# MSV-front.net
KiCad netlist of a schematic drawn in EAGLE
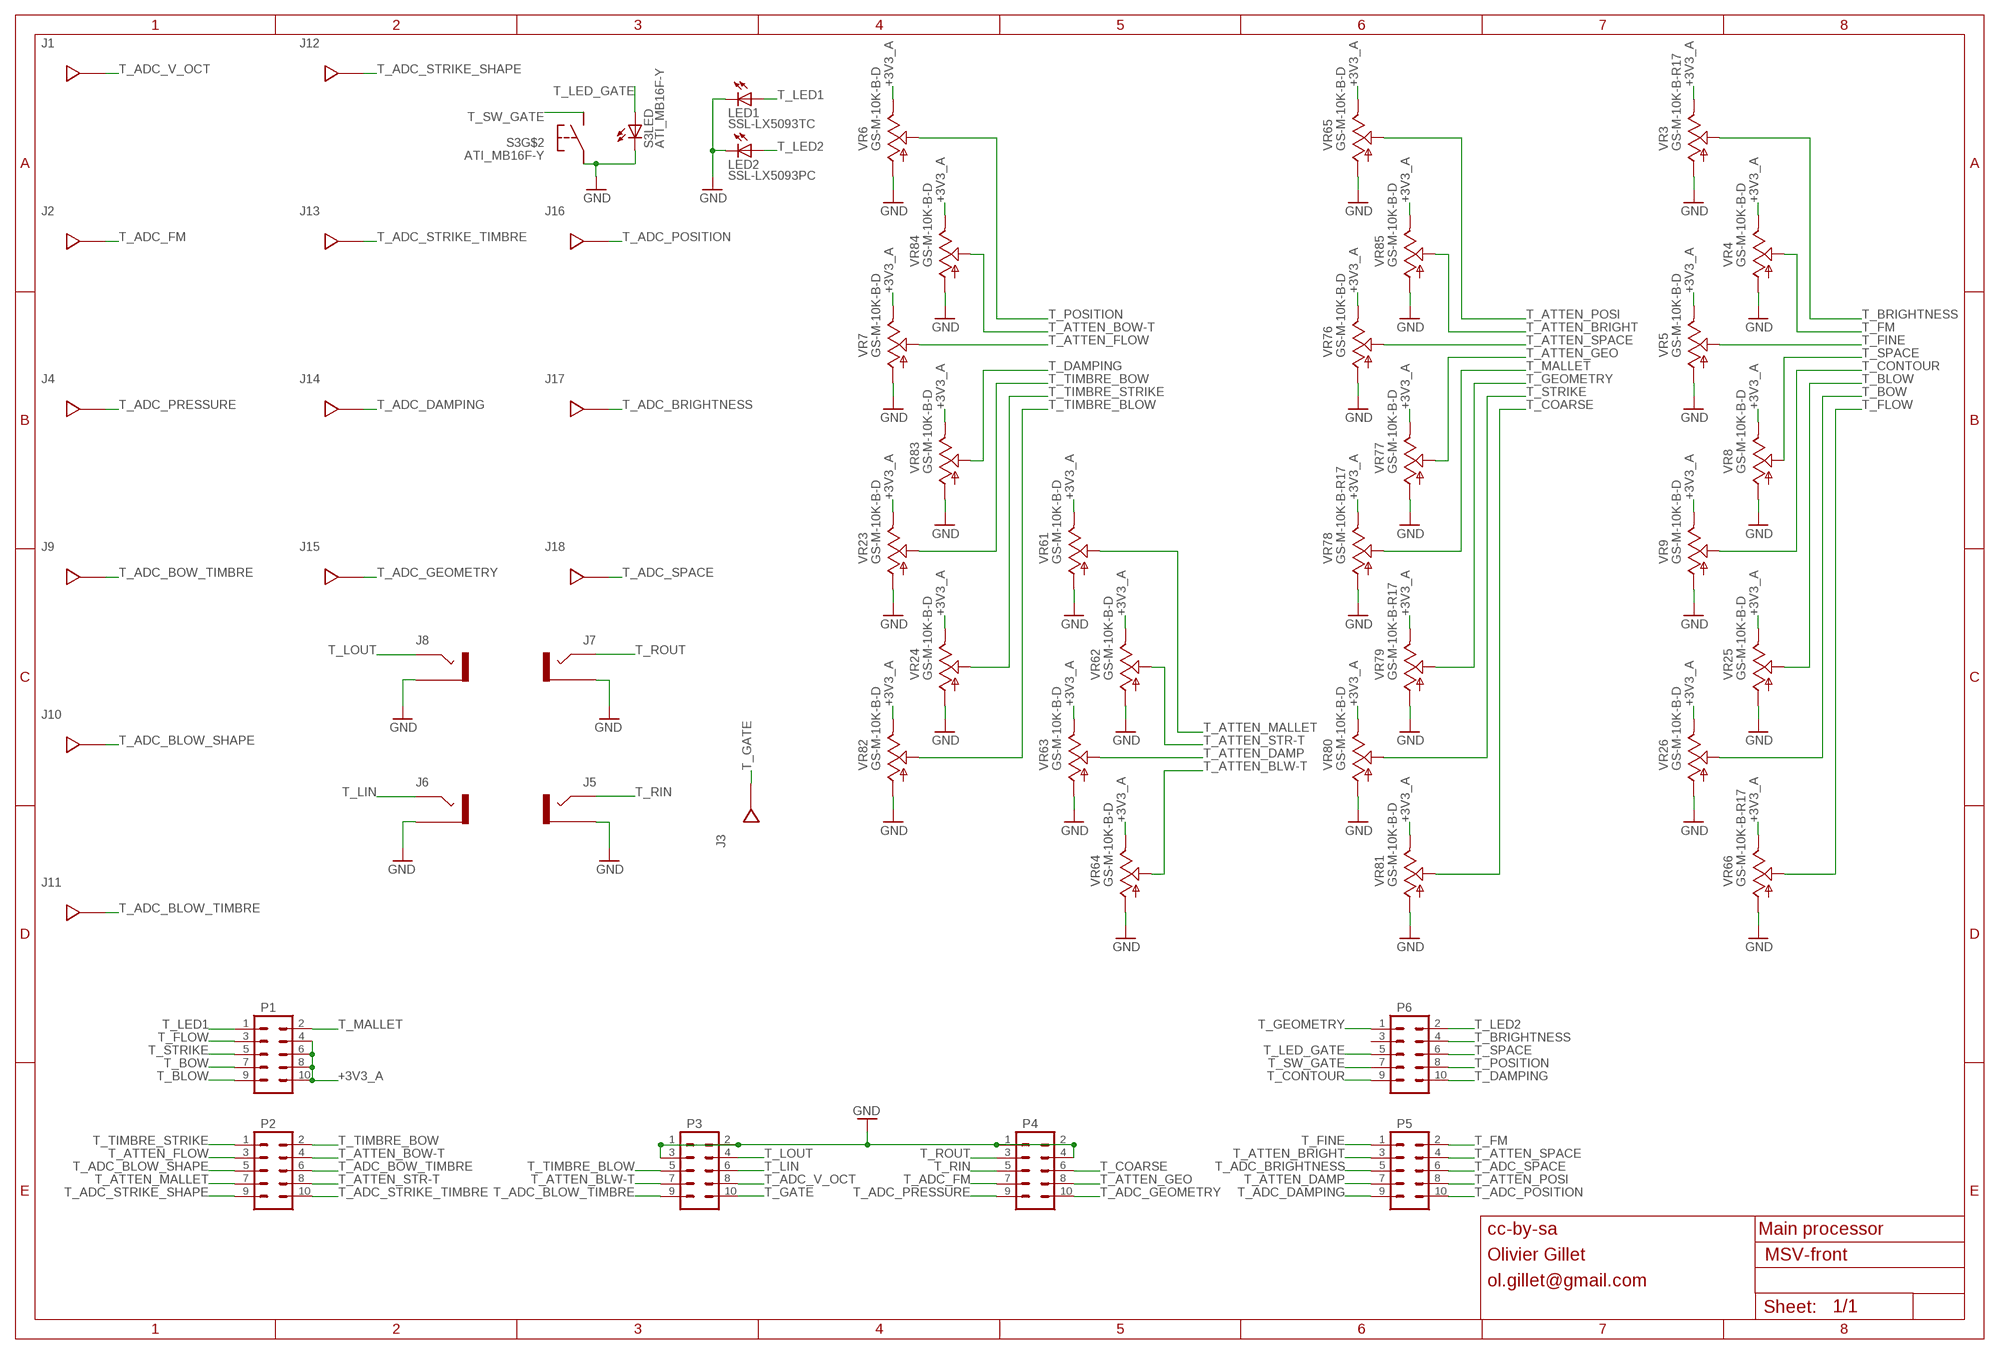
[diagram p0: schematic, sheet 1]

(export (version "E")
  (design (tool "Eeschema 10.0.6"))
  (components
    (comp (ref "J1")
      (value "BANANA_JACK_GRAY")
      (footprint "eagle-import:JOHNSON_SILK")
      (libsource (lib "eagle-import") (part "BANANA_JACK_GRAY"))
    )
    (comp (ref "J2")
      (value "BANANA_JACK_BLACK")
      (footprint "eagle-import:JOHNSON_SILK")
      (libsource (lib "eagle-import") (part "BANANA_JACK_BLACK"))
    )
    (comp (ref "J3")
      (value "BANANA_JACK_ORANGE")
      (footprint "eagle-import:JOHNSON_SILK")
      (libsource (lib "eagle-import") (part "BANANA_JACK_ORANGE"))
    )
    (comp (ref "J4")
      (value "BANANA_JACK_BLACK")
      (footprint "eagle-import:JOHNSON_SILK")
      (libsource (lib "eagle-import") (part "BANANA_JACK_BLACK"))
    )
    (comp (ref "J5")
      (value "BUCHLA_AUDIO_JACK_ALT")
      (footprint "eagle-import:AUDIO_ALT")
      (fields (field (name "LABEL") "RES"))
      (libsource (lib "eagle-import") (part "BUCHLA_AUDIO_JACK_ALT"))
    )
    (comp (ref "J6")
      (value "BUCHLA_AUDIO_JACK_ALT")
      (footprint "eagle-import:AUDIO_ALT")
      (fields (field (name "LABEL") "EXC"))
      (libsource (lib "eagle-import") (part "BUCHLA_AUDIO_JACK_ALT"))
    )
    (comp (ref "J7")
      (value "BUCHLA_AUDIO_JACK_ALT")
      (footprint "eagle-import:AUDIO_ALT")
      (fields (field (name "LABEL") "OUT2"))
      (libsource (lib "eagle-import") (part "BUCHLA_AUDIO_JACK_ALT"))
    )
    (comp (ref "J8")
      (value "BUCHLA_AUDIO_JACK_ALT")
      (footprint "eagle-import:AUDIO_ALT")
      (fields (field (name "LABEL") "OUT1"))
      (libsource (lib "eagle-import") (part "BUCHLA_AUDIO_JACK_ALT"))
    )
    (comp (ref "J9")
      (value "BANANA_JACK_BLACK")
      (footprint "eagle-import:JOHNSON_SILK")
      (libsource (lib "eagle-import") (part "BANANA_JACK_BLACK"))
    )
    (comp (ref "J10")
      (value "BANANA_JACK_BLACK")
      (footprint "eagle-import:JOHNSON_SILK")
      (libsource (lib "eagle-import") (part "BANANA_JACK_BLACK"))
    )
    (comp (ref "J11")
      (value "BANANA_JACK_BLACK")
      (footprint "eagle-import:JOHNSON_SILK")
      (libsource (lib "eagle-import") (part "BANANA_JACK_BLACK"))
    )
    (comp (ref "J12")
      (value "BANANA_JACK_BLACK")
      (footprint "eagle-import:JOHNSON_SILK")
      (libsource (lib "eagle-import") (part "BANANA_JACK_BLACK"))
    )
    (comp (ref "J13")
      (value "BANANA_JACK_BLACK")
      (footprint "eagle-import:JOHNSON_SILK")
      (libsource (lib "eagle-import") (part "BANANA_JACK_BLACK"))
    )
    (comp (ref "J14")
      (value "BANANA_JACK_BLACK")
      (footprint "eagle-import:JOHNSON_SILK")
      (libsource (lib "eagle-import") (part "BANANA_JACK_BLACK"))
    )
    (comp (ref "J15")
      (value "BANANA_JACK_BLACK")
      (footprint "eagle-import:JOHNSON_SILK")
      (libsource (lib "eagle-import") (part "BANANA_JACK_BLACK"))
    )
    (comp (ref "J16")
      (value "BANANA_JACK_BLACK")
      (footprint "eagle-import:JOHNSON_SILK")
      (libsource (lib "eagle-import") (part "BANANA_JACK_BLACK"))
    )
    (comp (ref "J17")
      (value "BANANA_JACK_BLACK")
      (footprint "eagle-import:JOHNSON_SILK")
      (libsource (lib "eagle-import") (part "BANANA_JACK_BLACK"))
    )
    (comp (ref "J18")
      (value "BANANA_JACK_BLACK")
      (footprint "eagle-import:JOHNSON_SILK")
      (libsource (lib "eagle-import") (part "BANANA_JACK_BLACK"))
    )
    (comp (ref "LED1")
      (value "SSL-LX5093TC")
      (footprint "eagle-import:LED_SILK")
      (libsource (lib "eagle-import") (part "LED_SILK"))
    )
    (comp (ref "LED2")
      (value "SSL-LX5093PC")
      (footprint "eagle-import:LED_SILK")
      (libsource (lib "eagle-import") (part "LED_SILK"))
    )
    (comp (ref "P1")
      (value "M05X2_LOCK_FEMALE")
      (footprint "eagle-import:2X5_LOCK_FEMALE")
      (libsource (lib "eagle-import") (part "M05X2_LOCK_FEMALE"))
    )
    (comp (ref "P2")
      (value "M05X2_LOCK_FEMALE")
      (footprint "eagle-import:2X5_LOCK_FEMALE")
      (libsource (lib "eagle-import") (part "M05X2_LOCK_FEMALE"))
    )
    (comp (ref "P3")
      (value "M05X2_LOCK_FEMALE")
      (footprint "eagle-import:2X5_LOCK_FEMALE")
      (libsource (lib "eagle-import") (part "M05X2_LOCK_FEMALE"))
    )
    (comp (ref "P4")
      (value "M05X2_LOCK_FEMALE")
      (footprint "eagle-import:2X5_LOCK_FEMALE")
      (libsource (lib "eagle-import") (part "M05X2_LOCK_FEMALE"))
    )
    (comp (ref "P5")
      (value "M05X2_LOCK_FEMALE")
      (footprint "eagle-import:2X5_LOCK_FEMALE")
      (libsource (lib "eagle-import") (part "M05X2_LOCK_FEMALE"))
    )
    (comp (ref "P6")
      (value "M05X2_LOCK_FEMALE")
      (footprint "eagle-import:2X5_LOCK_FEMALE")
      (libsource (lib "eagle-import") (part "M05X2_LOCK_FEMALE"))
    )
    (comp (ref "S3")
      (value "ATI_MB16F-Y")
      (footprint "eagle-import:MB16F_SILK")
      (libsource (lib "eagle-import") (part "ATI_MB16F-Y"))
    )
    (comp (ref "VR3")
      (value "GS-M-10K-B-R17")
      (footprint "eagle-import:9MM_SNAP-IN_POT_SILK")
      (libsource (lib "eagle-import") (part "POT_9MM_SNAP-IN__"))
    )
    (comp (ref "VR4")
      (value "GS-M-10K-B-D")
      (footprint "eagle-import:9MM_SNAP-IN_POT_SILK")
      (libsource (lib "eagle-import") (part "POT_9MM_SNAP-IN__"))
    )
    (comp (ref "VR5")
      (value "GS-M-10K-B-D")
      (footprint "eagle-import:9MM_SNAP-IN_POT_SILK")
      (libsource (lib "eagle-import") (part "POT_9MM_SNAP-IN__"))
    )
    (comp (ref "VR6")
      (value "GS-M-10K-B-D")
      (footprint "eagle-import:9MM_SNAP-IN_POT_SILK")
      (libsource (lib "eagle-import") (part "POT_9MM_SNAP-IN__"))
    )
    (comp (ref "VR7")
      (value "GS-M-10K-B-D")
      (footprint "eagle-import:9MM_SNAP-IN_POT_SILK")
      (libsource (lib "eagle-import") (part "POT_9MM_SNAP-IN__"))
    )
    (comp (ref "VR8")
      (value "GS-M-10K-B-D")
      (footprint "eagle-import:9MM_SNAP-IN_POT_SILK")
      (libsource (lib "eagle-import") (part "POT_9MM_SNAP-IN__"))
    )
    (comp (ref "VR9")
      (value "GS-M-10K-B-D")
      (footprint "eagle-import:9MM_SNAP-IN_POT_SILK")
      (libsource (lib "eagle-import") (part "POT_9MM_SNAP-IN__"))
    )
    (comp (ref "VR23")
      (value "GS-M-10K-B-D")
      (footprint "eagle-import:9MM_SNAP-IN_POT_SILK")
      (libsource (lib "eagle-import") (part "POT_9MM_SNAP-IN__"))
    )
    (comp (ref "VR24")
      (value "GS-M-10K-B-D")
      (footprint "eagle-import:9MM_SNAP-IN_POT_SILK")
      (libsource (lib "eagle-import") (part "POT_9MM_SNAP-IN__"))
    )
    (comp (ref "VR25")
      (value "GS-M-10K-B-D")
      (footprint "eagle-import:9MM_SNAP-IN_POT_SILK")
      (libsource (lib "eagle-import") (part "POT_9MM_SNAP-IN__"))
    )
    (comp (ref "VR26")
      (value "GS-M-10K-B-D")
      (footprint "eagle-import:9MM_SNAP-IN_POT_SILK")
      (libsource (lib "eagle-import") (part "POT_9MM_SNAP-IN__"))
    )
    (comp (ref "VR61")
      (value "GS-M-10K-B-D")
      (footprint "eagle-import:9MM_SNAP-IN_POT_SILK")
      (libsource (lib "eagle-import") (part "POT_9MM_SNAP-IN__"))
    )
    (comp (ref "VR62")
      (value "GS-M-10K-B-D")
      (footprint "eagle-import:9MM_SNAP-IN_POT_SILK")
      (libsource (lib "eagle-import") (part "POT_9MM_SNAP-IN__"))
    )
    (comp (ref "VR63")
      (value "GS-M-10K-B-D")
      (footprint "eagle-import:9MM_SNAP-IN_POT_SILK")
      (libsource (lib "eagle-import") (part "POT_9MM_SNAP-IN__"))
    )
    (comp (ref "VR64")
      (value "GS-M-10K-B-D")
      (footprint "eagle-import:9MM_SNAP-IN_POT_SILK")
      (libsource (lib "eagle-import") (part "POT_9MM_SNAP-IN__"))
    )
    (comp (ref "VR65")
      (value "GS-M-10K-B-D")
      (footprint "eagle-import:9MM_SNAP-IN_POT_SILK")
      (libsource (lib "eagle-import") (part "POT_9MM_SNAP-IN__"))
    )
    (comp (ref "VR66")
      (value "GS-M-10K-B-R17")
      (footprint "eagle-import:9MM_SNAP-IN_POT_SILK")
      (libsource (lib "eagle-import") (part "POT_9MM_SNAP-IN__"))
    )
    (comp (ref "VR76")
      (value "GS-M-10K-B-D")
      (footprint "eagle-import:9MM_SNAP-IN_POT_SILK")
      (libsource (lib "eagle-import") (part "POT_9MM_SNAP-IN__"))
    )
    (comp (ref "VR77")
      (value "GS-M-10K-B-D")
      (footprint "eagle-import:9MM_SNAP-IN_POT_SILK")
      (libsource (lib "eagle-import") (part "POT_9MM_SNAP-IN__"))
    )
    (comp (ref "VR78")
      (value "GS-M-10K-B-R17")
      (footprint "eagle-import:9MM_SNAP-IN_POT_SILK")
      (libsource (lib "eagle-import") (part "POT_9MM_SNAP-IN__"))
    )
    (comp (ref "VR79")
      (value "GS-M-10K-B-R17")
      (footprint "eagle-import:9MM_SNAP-IN_POT_SILK")
      (libsource (lib "eagle-import") (part "POT_9MM_SNAP-IN__"))
    )
    (comp (ref "VR80")
      (value "GS-M-10K-B-D")
      (footprint "eagle-import:9MM_SNAP-IN_POT_SILK")
      (libsource (lib "eagle-import") (part "POT_9MM_SNAP-IN__"))
    )
    (comp (ref "VR81")
      (value "GS-M-10K-B-D")
      (footprint "eagle-import:9MM_SNAP-IN_POT_SILK")
      (libsource (lib "eagle-import") (part "POT_9MM_SNAP-IN__"))
    )
    (comp (ref "VR82")
      (value "GS-M-10K-B-D")
      (footprint "eagle-import:9MM_SNAP-IN_POT_SILK")
      (libsource (lib "eagle-import") (part "POT_9MM_SNAP-IN__"))
    )
    (comp (ref "VR83")
      (value "GS-M-10K-B-D")
      (footprint "eagle-import:9MM_SNAP-IN_POT_SILK")
      (libsource (lib "eagle-import") (part "POT_9MM_SNAP-IN__"))
    )
    (comp (ref "VR84")
      (value "GS-M-10K-B-D")
      (footprint "eagle-import:9MM_SNAP-IN_POT_SILK")
      (libsource (lib "eagle-import") (part "POT_9MM_SNAP-IN__"))
    )
    (comp (ref "VR85")
      (value "GS-M-10K-B-D")
      (footprint "eagle-import:9MM_SNAP-IN_POT_SILK")
      (libsource (lib "eagle-import") (part "POT_9MM_SNAP-IN__"))
    )
  )
  (nets
    (net (code "1") (name "/+3V3_A") (class "Default")
      (node (ref "P1") (pin "10") (pinfunction "10_10") (pintype "passive"))
      (node (ref "P1") (pin "4") (pinfunction "4_4") (pintype "passive"))
      (node (ref "P1") (pin "6") (pinfunction "6_6") (pintype "passive"))
      (node (ref "P1") (pin "8") (pinfunction "8_8") (pintype "passive"))
      (node (ref "VR23") (pin "3") (pinfunction "3_3") (pintype "passive"))
      (node (ref "VR24") (pin "3") (pinfunction "3_3") (pintype "passive"))
      (node (ref "VR25") (pin "3") (pinfunction "3_3") (pintype "passive"))
      (node (ref "VR26") (pin "3") (pinfunction "3_3") (pintype "passive"))
      (node (ref "VR3") (pin "3") (pinfunction "3_3") (pintype "passive"))
      (node (ref "VR4") (pin "3") (pinfunction "3_3") (pintype "passive"))
      (node (ref "VR5") (pin "3") (pinfunction "3_3") (pintype "passive"))
      (node (ref "VR6") (pin "3") (pinfunction "3_3") (pintype "passive"))
      (node (ref "VR61") (pin "3") (pinfunction "3_3") (pintype "passive"))
      (node (ref "VR62") (pin "3") (pinfunction "3_3") (pintype "passive"))
      (node (ref "VR63") (pin "3") (pinfunction "3_3") (pintype "passive"))
      (node (ref "VR64") (pin "3") (pinfunction "3_3") (pintype "passive"))
      (node (ref "VR65") (pin "3") (pinfunction "3_3") (pintype "passive"))
      (node (ref "VR66") (pin "3") (pinfunction "3_3") (pintype "passive"))
      (node (ref "VR7") (pin "3") (pinfunction "3_3") (pintype "passive"))
      (node (ref "VR76") (pin "3") (pinfunction "3_3") (pintype "passive"))
      (node (ref "VR77") (pin "3") (pinfunction "3_3") (pintype "passive"))
      (node (ref "VR78") (pin "3") (pinfunction "3_3") (pintype "passive"))
      (node (ref "VR79") (pin "3") (pinfunction "3_3") (pintype "passive"))
      (node (ref "VR8") (pin "3") (pinfunction "3_3") (pintype "passive"))
      (node (ref "VR80") (pin "3") (pinfunction "3_3") (pintype "passive"))
      (node (ref "VR81") (pin "3") (pinfunction "3_3") (pintype "passive"))
      (node (ref "VR82") (pin "3") (pinfunction "3_3") (pintype "passive"))
      (node (ref "VR83") (pin "3") (pinfunction "3_3") (pintype "passive"))
      (node (ref "VR84") (pin "3") (pinfunction "3_3") (pintype "passive"))
      (node (ref "VR85") (pin "3") (pinfunction "3_3") (pintype "passive"))
      (node (ref "VR9") (pin "3") (pinfunction "3_3") (pintype "passive"))
    )
    (net (code "2") (name "/T_ADC_BLOW_SHAPE") (class "Default")
      (node (ref "J10") (pin "1") (pinfunction "1_1") (pintype "output"))
      (node (ref "P2") (pin "5") (pinfunction "5_5") (pintype "passive"))
    )
    (net (code "3") (name "/T_ADC_BLOW_TIMBRE") (class "Default")
      (node (ref "J11") (pin "1") (pinfunction "1_1") (pintype "output"))
      (node (ref "P3") (pin "9") (pinfunction "9_9") (pintype "passive"))
    )
    (net (code "4") (name "/T_ADC_BOW_TIMBRE") (class "Default")
      (node (ref "J9") (pin "1") (pinfunction "1_1") (pintype "output"))
      (node (ref "P2") (pin "6") (pinfunction "6_6") (pintype "passive"))
    )
    (net (code "5") (name "/T_ADC_BRIGHTNESS") (class "Default")
      (node (ref "J17") (pin "1") (pinfunction "1_1") (pintype "output"))
      (node (ref "P5") (pin "5") (pinfunction "5_5") (pintype "passive"))
    )
    (net (code "6") (name "/T_ADC_DAMPING") (class "Default")
      (node (ref "J14") (pin "1") (pinfunction "1_1") (pintype "output"))
      (node (ref "P5") (pin "9") (pinfunction "9_9") (pintype "passive"))
    )
    (net (code "7") (name "/T_ADC_FM") (class "Default")
      (node (ref "J2") (pin "1") (pinfunction "1_1") (pintype "output"))
      (node (ref "P4") (pin "7") (pinfunction "7_7") (pintype "passive"))
    )
    (net (code "8") (name "/T_ADC_GEOMETRY") (class "Default")
      (node (ref "J15") (pin "1") (pinfunction "1_1") (pintype "output"))
      (node (ref "P4") (pin "10") (pinfunction "10_10") (pintype "passive"))
    )
    (net (code "9") (name "/T_ADC_POSITION") (class "Default")
      (node (ref "J16") (pin "1") (pinfunction "1_1") (pintype "output"))
      (node (ref "P5") (pin "10") (pinfunction "10_10") (pintype "passive"))
    )
    (net (code "10") (name "/T_ADC_PRESSURE") (class "Default")
      (node (ref "J4") (pin "1") (pinfunction "1_1") (pintype "output"))
      (node (ref "P4") (pin "9") (pinfunction "9_9") (pintype "passive"))
    )
    (net (code "11") (name "/T_ADC_SPACE") (class "Default")
      (node (ref "J18") (pin "1") (pinfunction "1_1") (pintype "output"))
      (node (ref "P5") (pin "6") (pinfunction "6_6") (pintype "passive"))
    )
    (net (code "12") (name "/T_ADC_STRIKE_SHAPE") (class "Default")
      (node (ref "J12") (pin "1") (pinfunction "1_1") (pintype "output"))
      (node (ref "P2") (pin "9") (pinfunction "9_9") (pintype "passive"))
    )
    (net (code "13") (name "/T_ADC_STRIKE_TIMBRE") (class "Default")
      (node (ref "J13") (pin "1") (pinfunction "1_1") (pintype "output"))
      (node (ref "P2") (pin "10") (pinfunction "10_10") (pintype "passive"))
    )
    (net (code "14") (name "/T_ADC_V_OCT") (class "Default")
      (node (ref "J1") (pin "1") (pinfunction "1_1") (pintype "output"))
      (node (ref "P3") (pin "8") (pinfunction "8_8") (pintype "passive"))
    )
    (net (code "15") (name "/T_ATTEN_BLW-T") (class "Default")
      (node (ref "P3") (pin "7") (pinfunction "7_7") (pintype "passive"))
      (node (ref "VR64") (pin "2") (pinfunction "2_2") (pintype "passive"))
    )
    (net (code "16") (name "/T_ATTEN_BOW-T") (class "Default")
      (node (ref "P2") (pin "4") (pinfunction "4_4") (pintype "passive"))
      (node (ref "VR84") (pin "2") (pinfunction "2_2") (pintype "passive"))
    )
    (net (code "17") (name "/T_ATTEN_BRIGHT") (class "Default")
      (node (ref "P5") (pin "3") (pinfunction "3_3") (pintype "passive"))
      (node (ref "VR85") (pin "2") (pinfunction "2_2") (pintype "passive"))
    )
    (net (code "18") (name "/T_ATTEN_DAMP") (class "Default")
      (node (ref "P5") (pin "7") (pinfunction "7_7") (pintype "passive"))
      (node (ref "VR63") (pin "2") (pinfunction "2_2") (pintype "passive"))
    )
    (net (code "19") (name "/T_ATTEN_FLOW") (class "Default")
      (node (ref "P2") (pin "3") (pinfunction "3_3") (pintype "passive"))
      (node (ref "VR7") (pin "2") (pinfunction "2_2") (pintype "passive"))
    )
    (net (code "20") (name "/T_ATTEN_GEO") (class "Default")
      (node (ref "P4") (pin "8") (pinfunction "8_8") (pintype "passive"))
      (node (ref "VR77") (pin "2") (pinfunction "2_2") (pintype "passive"))
    )
    (net (code "21") (name "/T_ATTEN_MALLET") (class "Default")
      (node (ref "P2") (pin "7") (pinfunction "7_7") (pintype "passive"))
      (node (ref "VR61") (pin "2") (pinfunction "2_2") (pintype "passive"))
    )
    (net (code "22") (name "/T_ATTEN_POSI") (class "Default")
      (node (ref "P5") (pin "8") (pinfunction "8_8") (pintype "passive"))
      (node (ref "VR65") (pin "2") (pinfunction "2_2") (pintype "passive"))
    )
    (net (code "23") (name "/T_ATTEN_SPACE") (class "Default")
      (node (ref "P5") (pin "4") (pinfunction "4_4") (pintype "passive"))
      (node (ref "VR76") (pin "2") (pinfunction "2_2") (pintype "passive"))
    )
    (net (code "24") (name "/T_ATTEN_STR-T") (class "Default")
      (node (ref "P2") (pin "8") (pinfunction "8_8") (pintype "passive"))
      (node (ref "VR62") (pin "2") (pinfunction "2_2") (pintype "passive"))
    )
    (net (code "25") (name "/T_BLOW") (class "Default")
      (node (ref "P1") (pin "9") (pinfunction "9_9") (pintype "passive"))
      (node (ref "VR25") (pin "2") (pinfunction "2_2") (pintype "passive"))
    )
    (net (code "26") (name "/T_BOW") (class "Default")
      (node (ref "P1") (pin "7") (pinfunction "7_7") (pintype "passive"))
      (node (ref "VR26") (pin "2") (pinfunction "2_2") (pintype "passive"))
    )
    (net (code "27") (name "/T_BRIGHTNESS") (class "Default")
      (node (ref "P6") (pin "4") (pinfunction "4_4") (pintype "passive"))
      (node (ref "VR3") (pin "2") (pinfunction "2_2") (pintype "passive"))
    )
    (net (code "28") (name "/T_COARSE") (class "Default")
      (node (ref "P4") (pin "6") (pinfunction "6_6") (pintype "passive"))
      (node (ref "VR81") (pin "2") (pinfunction "2_2") (pintype "passive"))
    )
    (net (code "29") (name "/T_CONTOUR") (class "Default")
      (node (ref "P6") (pin "9") (pinfunction "9_9") (pintype "passive"))
      (node (ref "VR9") (pin "2") (pinfunction "2_2") (pintype "passive"))
    )
    (net (code "30") (name "/T_DAMPING") (class "Default")
      (node (ref "P6") (pin "10") (pinfunction "10_10") (pintype "passive"))
      (node (ref "VR83") (pin "2") (pinfunction "2_2") (pintype "passive"))
    )
    (net (code "31") (name "/T_FINE") (class "Default")
      (node (ref "P5") (pin "1") (pinfunction "1_1") (pintype "passive"))
      (node (ref "VR5") (pin "2") (pinfunction "2_2") (pintype "passive"))
    )
    (net (code "32") (name "/T_FLOW") (class "Default")
      (node (ref "P1") (pin "3") (pinfunction "3_3") (pintype "passive"))
      (node (ref "VR66") (pin "2") (pinfunction "2_2") (pintype "passive"))
    )
    (net (code "33") (name "/T_FM") (class "Default")
      (node (ref "P5") (pin "2") (pinfunction "2_2") (pintype "passive"))
      (node (ref "VR4") (pin "2") (pinfunction "2_2") (pintype "passive"))
    )
    (net (code "34") (name "/T_GATE") (class "Default")
      (node (ref "J3") (pin "1") (pinfunction "1_1") (pintype "output"))
      (node (ref "P3") (pin "10") (pinfunction "10_10") (pintype "passive"))
    )
    (net (code "35") (name "/T_GEOMETRY") (class "Default")
      (node (ref "P6") (pin "1") (pinfunction "1_1") (pintype "passive"))
      (node (ref "VR79") (pin "2") (pinfunction "2_2") (pintype "passive"))
    )
    (net (code "36") (name "/T_LED1") (class "Default")
      (node (ref "LED1") (pin "A") (pinfunction "A_A") (pintype "passive"))
      (node (ref "P1") (pin "1") (pinfunction "1_1") (pintype "passive"))
    )
    (net (code "37") (name "/T_LED2") (class "Default")
      (node (ref "LED2") (pin "A") (pinfunction "A_A") (pintype "passive"))
      (node (ref "P6") (pin "2") (pinfunction "2_2") (pintype "passive"))
    )
    (net (code "38") (name "/T_LED_GATE") (class "Default")
      (node (ref "P6") (pin "5") (pinfunction "5_5") (pintype "passive"))
      (node (ref "S3") (pin "3") (pinfunction "L1_3") (pintype "passive"))
    )
    (net (code "39") (name "/T_LIN") (class "Default")
      (node (ref "J6") (pin "S") (pinfunction "1_S") (pintype "bidirectional"))
      (node (ref "P3") (pin "6") (pinfunction "6_6") (pintype "passive"))
    )
    (net (code "40") (name "/T_LOUT") (class "Default")
      (node (ref "J8") (pin "S") (pinfunction "1_S") (pintype "bidirectional"))
      (node (ref "P3") (pin "4") (pinfunction "4_4") (pintype "passive"))
    )
    (net (code "41") (name "/T_MALLET") (class "Default")
      (node (ref "P1") (pin "2") (pinfunction "2_2") (pintype "passive"))
      (node (ref "VR78") (pin "2") (pinfunction "2_2") (pintype "passive"))
    )
    (net (code "42") (name "/T_POSITION") (class "Default")
      (node (ref "P6") (pin "8") (pinfunction "8_8") (pintype "passive"))
      (node (ref "VR6") (pin "2") (pinfunction "2_2") (pintype "passive"))
    )
    (net (code "43") (name "/T_RIN") (class "Default")
      (node (ref "J5") (pin "S") (pinfunction "1_S") (pintype "bidirectional"))
      (node (ref "P4") (pin "5") (pinfunction "5_5") (pintype "passive"))
    )
    (net (code "44") (name "/T_ROUT") (class "Default")
      (node (ref "J7") (pin "S") (pinfunction "1_S") (pintype "bidirectional"))
      (node (ref "P4") (pin "3") (pinfunction "3_3") (pintype "passive"))
    )
    (net (code "45") (name "/T_SPACE") (class "Default")
      (node (ref "P6") (pin "6") (pinfunction "6_6") (pintype "passive"))
      (node (ref "VR8") (pin "2") (pinfunction "2_2") (pintype "passive"))
    )
    (net (code "46") (name "/T_STRIKE") (class "Default")
      (node (ref "P1") (pin "5") (pinfunction "5_5") (pintype "passive"))
      (node (ref "VR80") (pin "2") (pinfunction "2_2") (pintype "passive"))
    )
    (net (code "47") (name "/T_SW_GATE") (class "Default")
      (node (ref "P6") (pin "7") (pinfunction "7_7") (pintype "passive"))
      (node (ref "S3") (pin "1") (pinfunction "2_1") (pintype "passive"))
    )
    (net (code "48") (name "/T_TIMBRE_BLOW") (class "Default")
      (node (ref "P3") (pin "5") (pinfunction "5_5") (pintype "passive"))
      (node (ref "VR82") (pin "2") (pinfunction "2_2") (pintype "passive"))
    )
    (net (code "49") (name "/T_TIMBRE_BOW") (class "Default")
      (node (ref "P2") (pin "2") (pinfunction "2_2") (pintype "passive"))
      (node (ref "VR23") (pin "2") (pinfunction "2_2") (pintype "passive"))
    )
    (net (code "50") (name "/T_TIMBRE_STRIKE") (class "Default")
      (node (ref "P2") (pin "1") (pinfunction "1_1") (pintype "passive"))
      (node (ref "VR24") (pin "2") (pinfunction "2_2") (pintype "passive"))
    )
    (net (code "51") (name "GND") (class "Default")
      (node (ref "J5") (pin "G") (pinfunction "2_G") (pintype "bidirectional"))
      (node (ref "J6") (pin "G") (pinfunction "2_G") (pintype "bidirectional"))
      (node (ref "J7") (pin "G") (pinfunction "2_G") (pintype "bidirectional"))
      (node (ref "J8") (pin "G") (pinfunction "2_G") (pintype "bidirectional"))
      (node (ref "LED1") (pin "K") (pinfunction "C_K") (pintype "passive"))
      (node (ref "LED2") (pin "K") (pinfunction "C_K") (pintype "passive"))
      (node (ref "P3") (pin "1") (pinfunction "1_1") (pintype "passive"))
      (node (ref "P3") (pin "2") (pinfunction "2_2") (pintype "passive"))
      (node (ref "P3") (pin "3") (pinfunction "3_3") (pintype "passive"))
      (node (ref "P4") (pin "1") (pinfunction "1_1") (pintype "passive"))
      (node (ref "P4") (pin "2") (pinfunction "2_2") (pintype "passive"))
      (node (ref "P4") (pin "4") (pinfunction "4_4") (pintype "passive"))
      (node (ref "S3") (pin "2") (pinfunction "1_2") (pintype "passive"))
      (node (ref "S3") (pin "4") (pinfunction "L2_4") (pintype "passive"))
      (node (ref "VR23") (pin "1") (pinfunction "1_1") (pintype "passive"))
      (node (ref "VR24") (pin "1") (pinfunction "1_1") (pintype "passive"))
      (node (ref "VR25") (pin "1") (pinfunction "1_1") (pintype "passive"))
      (node (ref "VR26") (pin "1") (pinfunction "1_1") (pintype "passive"))
      (node (ref "VR3") (pin "1") (pinfunction "1_1") (pintype "passive"))
      (node (ref "VR4") (pin "1") (pinfunction "1_1") (pintype "passive"))
      (node (ref "VR5") (pin "1") (pinfunction "1_1") (pintype "passive"))
      (node (ref "VR6") (pin "1") (pinfunction "1_1") (pintype "passive"))
      (node (ref "VR61") (pin "1") (pinfunction "1_1") (pintype "passive"))
      (node (ref "VR62") (pin "1") (pinfunction "1_1") (pintype "passive"))
      (node (ref "VR63") (pin "1") (pinfunction "1_1") (pintype "passive"))
      (node (ref "VR64") (pin "1") (pinfunction "1_1") (pintype "passive"))
      (node (ref "VR65") (pin "1") (pinfunction "1_1") (pintype "passive"))
      (node (ref "VR66") (pin "1") (pinfunction "1_1") (pintype "passive"))
      (node (ref "VR7") (pin "1") (pinfunction "1_1") (pintype "passive"))
      (node (ref "VR76") (pin "1") (pinfunction "1_1") (pintype "passive"))
      (node (ref "VR77") (pin "1") (pinfunction "1_1") (pintype "passive"))
      (node (ref "VR78") (pin "1") (pinfunction "1_1") (pintype "passive"))
      (node (ref "VR79") (pin "1") (pinfunction "1_1") (pintype "passive"))
      (node (ref "VR8") (pin "1") (pinfunction "1_1") (pintype "passive"))
      (node (ref "VR80") (pin "1") (pinfunction "1_1") (pintype "passive"))
      (node (ref "VR81") (pin "1") (pinfunction "1_1") (pintype "passive"))
      (node (ref "VR82") (pin "1") (pinfunction "1_1") (pintype "passive"))
      (node (ref "VR83") (pin "1") (pinfunction "1_1") (pintype "passive"))
      (node (ref "VR84") (pin "1") (pinfunction "1_1") (pintype "passive"))
      (node (ref "VR85") (pin "1") (pinfunction "1_1") (pintype "passive"))
      (node (ref "VR9") (pin "1") (pinfunction "1_1") (pintype "passive"))
    )
    (net (code "52") (name "unconnected-(P6-Pad3)") (class "Default")
      (node (ref "P6") (pin "3") (pinfunction "3_3") (pintype "passive"))
    )
  )
)
